# Ethernet.net
KiCad netlist of a schematic drawn in Altium Designer
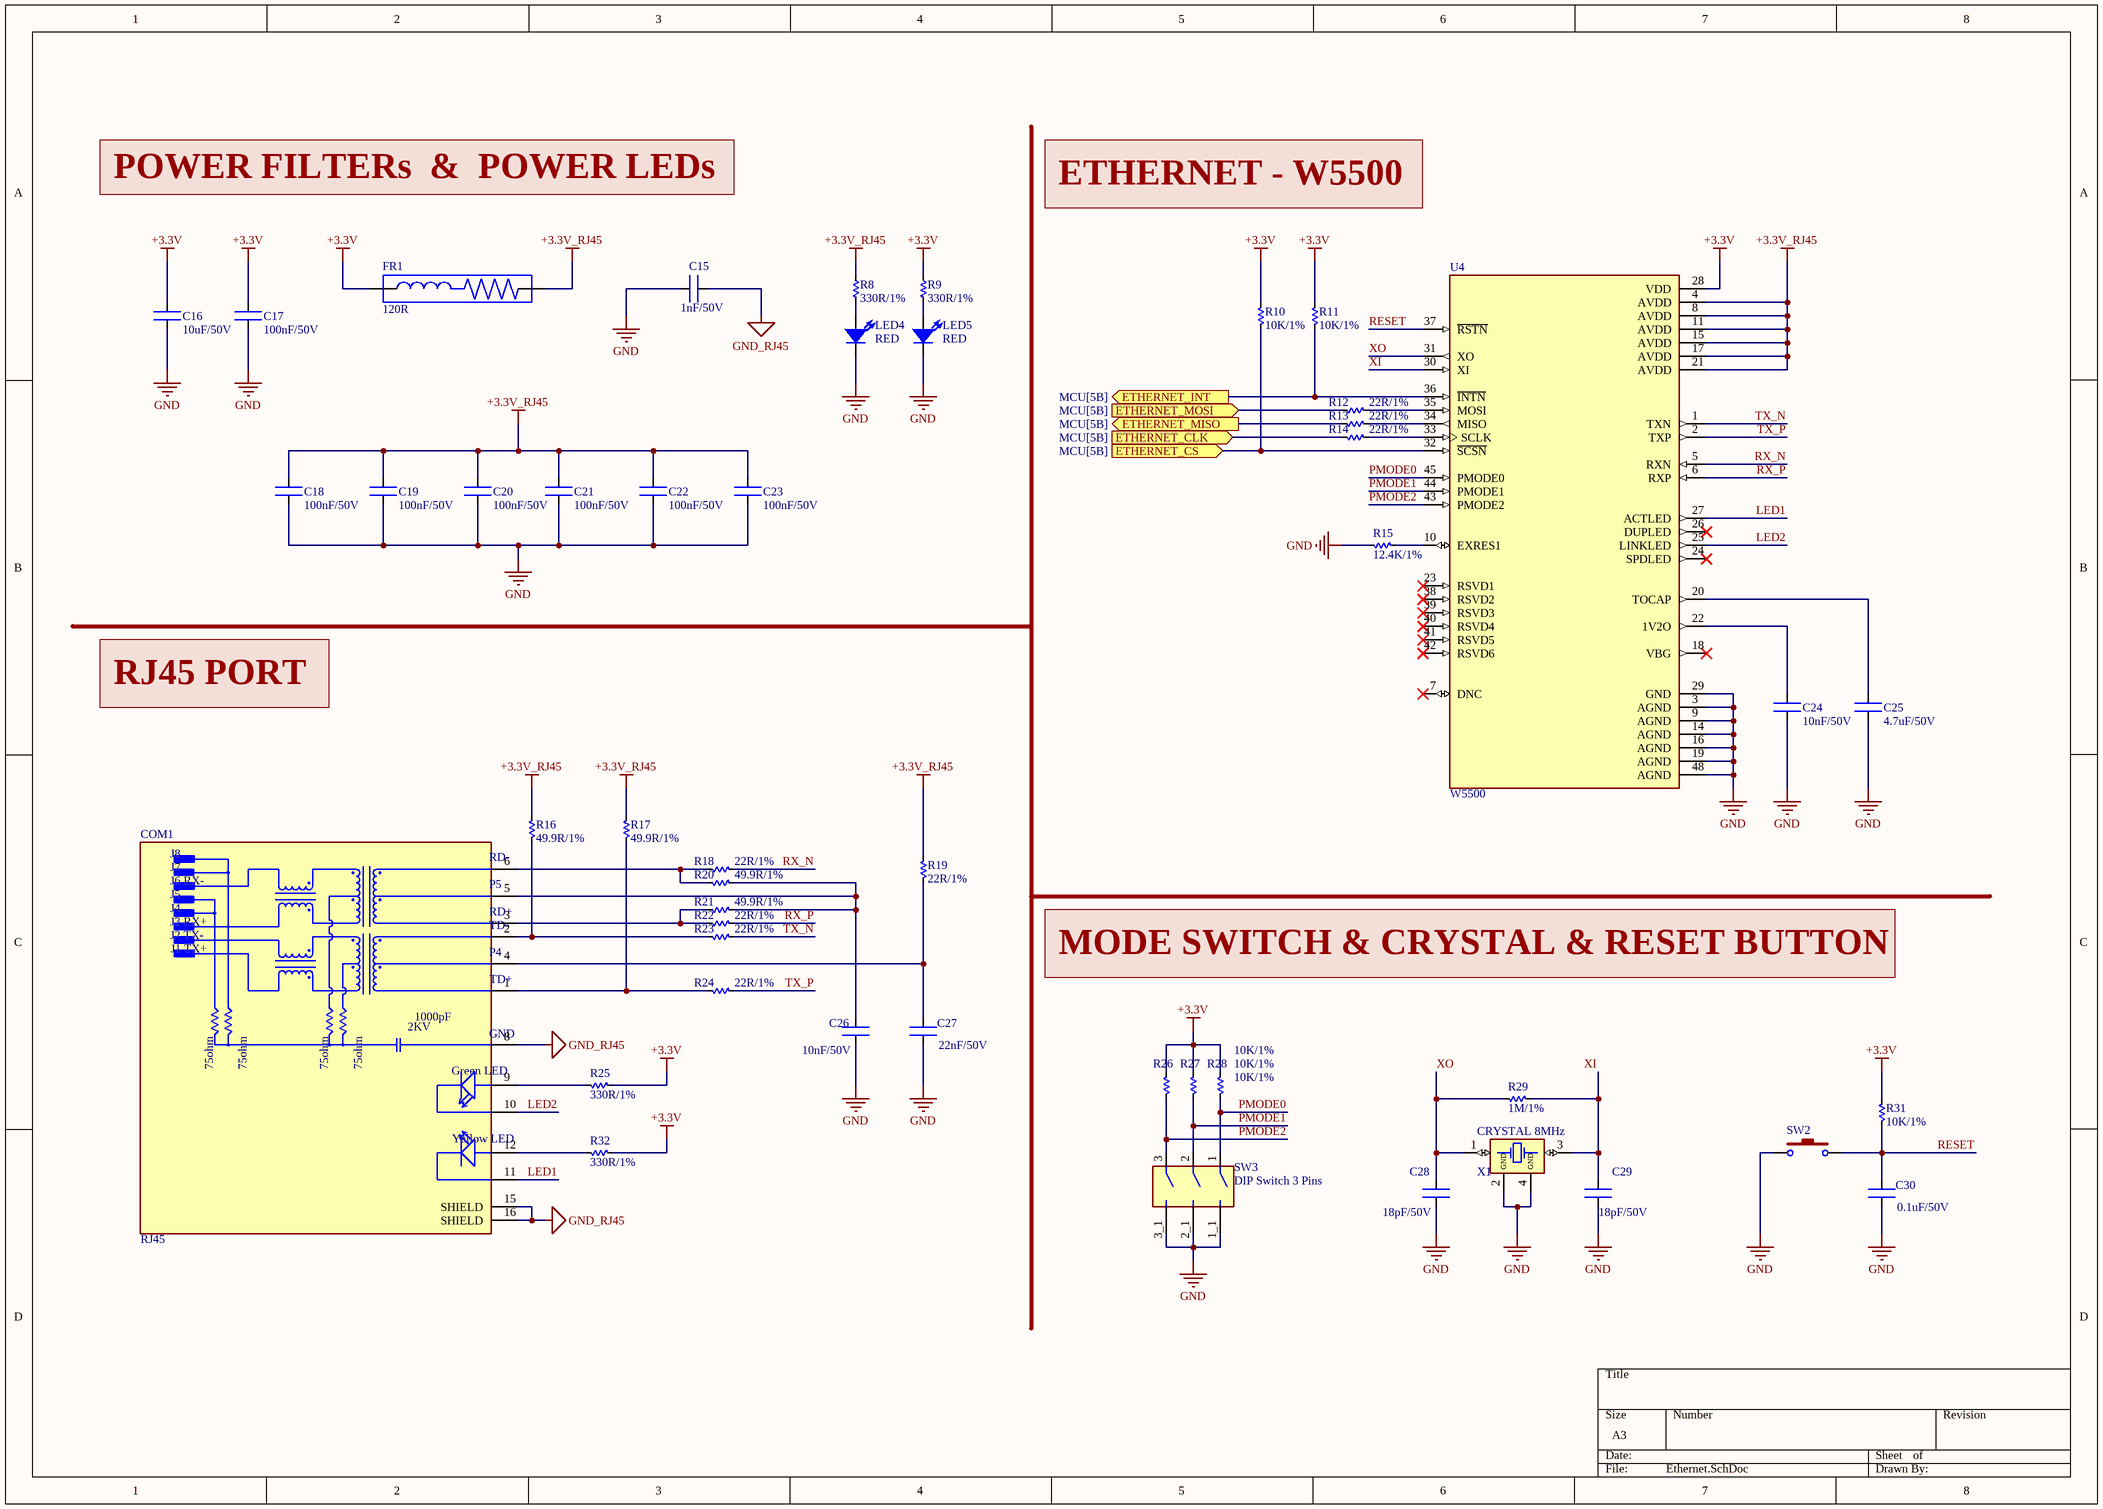
[diagram p0: Ethernet.SchDoc]

(export (version "E")
  (design (tool "Eeschema 10.0.6"))
  (components
    (comp (ref "C15")
      (value "1nF/50V")
      (footprint "CAP - 0603")
      (description "CAPACITOR SMD - KEMET")
      (libsource (lib "NewLibrary") (part "CAPACITOR"))
    )
    (comp (ref "C16")
      (value "10uF/50V")
      (footprint "CAP - 0603")
      (description "CAPACITOR SMD - KEMET")
      (libsource (lib "NewLibrary") (part "CAPACITOR"))
    )
    (comp (ref "C17")
      (value "100nF/50V")
      (footprint "CAP - 0603")
      (description "CAPACITOR SMD - KEMET")
      (libsource (lib "NewLibrary") (part "CAPACITOR"))
    )
    (comp (ref "C18")
      (value "100nF/50V")
      (footprint "CAP - 0603")
      (description "CAPACITOR SMD - KEMET")
      (libsource (lib "NewLibrary") (part "CAPACITOR"))
    )
    (comp (ref "C19")
      (value "100nF/50V")
      (footprint "CAP - 0603")
      (description "CAPACITOR SMD - KEMET")
      (libsource (lib "NewLibrary") (part "CAPACITOR"))
    )
    (comp (ref "C20")
      (value "100nF/50V")
      (footprint "CAP - 0603")
      (description "CAPACITOR SMD - KEMET")
      (libsource (lib "NewLibrary") (part "CAPACITOR"))
    )
    (comp (ref "C21")
      (value "100nF/50V")
      (footprint "CAP - 0603")
      (description "CAPACITOR SMD - KEMET")
      (libsource (lib "NewLibrary") (part "CAPACITOR"))
    )
    (comp (ref "C22")
      (value "100nF/50V")
      (footprint "CAP - 0603")
      (description "CAPACITOR SMD - KEMET")
      (libsource (lib "NewLibrary") (part "CAPACITOR"))
    )
    (comp (ref "C23")
      (value "100nF/50V")
      (footprint "CAP - 0603")
      (description "CAPACITOR SMD - KEMET")
      (libsource (lib "NewLibrary") (part "CAPACITOR"))
    )
    (comp (ref "C24")
      (value "10nF/50V")
      (footprint "CAP - 0603")
      (description "CAPACITOR SMD - KEMET")
      (libsource (lib "NewLibrary") (part "CAPACITOR"))
    )
    (comp (ref "C25")
      (value "4.7uF/50V")
      (footprint "CAP - 0603")
      (description "CAPACITOR SMD - KEMET")
      (libsource (lib "NewLibrary") (part "CAPACITOR"))
    )
    (comp (ref "C26")
      (value "10nF/50V")
      (footprint "CAP - 0603")
      (description "CAPACITOR SMD - KEMET")
      (libsource (lib "NewLibrary") (part "CAPACITOR"))
    )
    (comp (ref "C27")
      (value "22nF/50V")
      (footprint "CAP - 0603")
      (description "CAPACITOR SMD - KEMET")
      (libsource (lib "NewLibrary") (part "CAPACITOR"))
    )
    (comp (ref "C28")
      (value "18pF/50V")
      (footprint "CAP - 0603")
      (description "CAPACITOR SMD - KEMET")
      (libsource (lib "NewLibrary") (part "CAPACITOR"))
    )
    (comp (ref "C29")
      (value "18pF/50V")
      (footprint "CAP - 0603")
      (description "CAPACITOR SMD - KEMET")
      (libsource (lib "NewLibrary") (part "CAPACITOR"))
    )
    (comp (ref "C30")
      (value "0.1uF/50V")
      (footprint "CAP - 0603")
      (description "CAPACITOR SMD - KEMET")
      (libsource (lib "NewLibrary") (part "CAPACITOR"))
    )
    (comp (ref "COM1")
      (value "RJ45")
      (footprint "RJ45")
      (description "HR911105A")
      (libsource (lib "NewLibrary") (part "RJ45"))
    )
    (comp (ref "FR1")
      (value "120R")
      (footprint "FR-0805")
      (description "SMD")
      (libsource (lib "NewLibrary") (part "Ferrite Beads"))
    )
    (comp (ref "LED4")
      (value "RED")
      (footprint "RED_LED_0603")
      (description "LED SMD")
      (libsource (lib "NewLibrary") (part "LED_SMD"))
    )
    (comp (ref "LED5")
      (value "RED")
      (footprint "RED_LED_0603")
      (description "LED SMD")
      (libsource (lib "NewLibrary") (part "LED_SMD"))
    )
    (comp (ref "R8")
      (value "330R/1%")
      (footprint "RES - 0603")
      (description "Resistor SMD - YAGEO")
      (libsource (lib "NewLibrary") (part "RESISTOR"))
    )
    (comp (ref "R9")
      (value "330R/1%")
      (footprint "RES - 0603")
      (description "Resistor SMD - YAGEO")
      (libsource (lib "NewLibrary") (part "RESISTOR"))
    )
    (comp (ref "R10")
      (value "10K/1%")
      (footprint "RES - 0603")
      (description "Resistor SMD - YAGEO")
      (libsource (lib "NewLibrary") (part "RESISTOR"))
    )
    (comp (ref "R11")
      (value "10K/1%")
      (footprint "RES - 0603")
      (description "Resistor SMD - YAGEO")
      (libsource (lib "NewLibrary") (part "RESISTOR"))
    )
    (comp (ref "R12")
      (value "22R/1%")
      (footprint "RES - 0603")
      (description "Resistor SMD - YAGEO")
      (libsource (lib "NewLibrary") (part "RESISTOR"))
    )
    (comp (ref "R13")
      (value "22R/1%")
      (footprint "RES - 0603")
      (description "Resistor SMD - YAGEO")
      (libsource (lib "NewLibrary") (part "RESISTOR"))
    )
    (comp (ref "R14")
      (value "22R/1%")
      (footprint "RES - 0603")
      (description "Resistor SMD - YAGEO")
      (libsource (lib "NewLibrary") (part "RESISTOR"))
    )
    (comp (ref "R15")
      (value "12.4K/1%")
      (footprint "RES - 0603")
      (description "Resistor SMD - YAGEO")
      (libsource (lib "NewLibrary") (part "RESISTOR"))
    )
    (comp (ref "R16")
      (value "49.9R/1%")
      (footprint "RES - 0603")
      (description "Resistor SMD - YAGEO")
      (libsource (lib "NewLibrary") (part "RESISTOR"))
    )
    (comp (ref "R17")
      (value "49.9R/1%")
      (footprint "RES - 0603")
      (description "Resistor SMD - YAGEO")
      (libsource (lib "NewLibrary") (part "RESISTOR"))
    )
    (comp (ref "R18")
      (value "22R/1%")
      (footprint "RES - 0603")
      (description "Resistor SMD - YAGEO")
      (libsource (lib "NewLibrary") (part "RESISTOR"))
    )
    (comp (ref "R19")
      (value "22R/1%")
      (footprint "RES - 0603")
      (description "Resistor SMD - YAGEO")
      (libsource (lib "NewLibrary") (part "RESISTOR"))
    )
    (comp (ref "R20")
      (value "49.9R/1%")
      (footprint "RES - 0603")
      (description "Resistor SMD - YAGEO")
      (libsource (lib "NewLibrary") (part "RESISTOR"))
    )
    (comp (ref "R21")
      (value "49.9R/1%")
      (footprint "RES - 0603")
      (description "Resistor SMD - YAGEO")
      (libsource (lib "NewLibrary") (part "RESISTOR"))
    )
    (comp (ref "R22")
      (value "22R/1%")
      (footprint "RES - 0603")
      (description "Resistor SMD - YAGEO")
      (libsource (lib "NewLibrary") (part "RESISTOR"))
    )
    (comp (ref "R23")
      (value "22R/1%")
      (footprint "RES - 0603")
      (description "Resistor SMD - YAGEO")
      (libsource (lib "NewLibrary") (part "RESISTOR"))
    )
    (comp (ref "R24")
      (value "22R/1%")
      (footprint "RES - 0603")
      (description "Resistor SMD - YAGEO")
      (libsource (lib "NewLibrary") (part "RESISTOR"))
    )
    (comp (ref "R25")
      (value "330R/1%")
      (footprint "RES - 0603")
      (description "Resistor SMD - YAGEO")
      (libsource (lib "NewLibrary") (part "RESISTOR"))
    )
    (comp (ref "R26")
      (value "10K/1%")
      (footprint "RES - 0603")
      (description "Resistor SMD - YAGEO")
      (libsource (lib "NewLibrary") (part "RESISTOR"))
    )
    (comp (ref "R27")
      (value "10K/1%")
      (footprint "RES - 0603")
      (description "Resistor SMD - YAGEO")
      (libsource (lib "NewLibrary") (part "RESISTOR"))
    )
    (comp (ref "R28")
      (value "10K/1%")
      (footprint "RES - 0603")
      (description "Resistor SMD - YAGEO")
      (libsource (lib "NewLibrary") (part "RESISTOR"))
    )
    (comp (ref "R29")
      (value "1M/1%")
      (footprint "RES - 0603")
      (description "Resistor SMD - YAGEO")
      (libsource (lib "NewLibrary") (part "RESISTOR"))
    )
    (comp (ref "R31")
      (value "10K/1%")
      (footprint "RES - 0603")
      (description "Resistor SMD - YAGEO")
      (libsource (lib "NewLibrary") (part "RESISTOR"))
    )
    (comp (ref "R32")
      (value "330R/1%")
      (footprint "RES - 0603")
      (description "Resistor SMD - YAGEO")
      (libsource (lib "NewLibrary") (part "RESISTOR"))
    )
    (comp (ref "SW2")
      (value "Button 2 Pins")
      (footprint "SMD SWITCH 2 PINS")
      (description "SMD Button")
      (libsource (lib "NewLibrary") (part "Button 2 Pins"))
    )
    (comp (ref "SW3")
      (value "DIP Switch 3 Pins")
      (footprint "SMD - SW - 3Pins")
      (description "Switch DIP ON OFF SPST 3 Flush Slide 0.1A 20VDC Gull Wing 2000Cycles 2.54mm SMD T/R")
      (libsource (lib "NewLibrary") (part "DIP Switch 3 Pins"))
    )
    (comp (ref "U4")
      (value "W5500")
      (footprint "LQFP-48")
      (description "Hardwired TCP/IP embedded Ethernet controller")
      (libsource (lib "NewLibrary") (part "W5500"))
    )
    (comp (ref "X1")
      (value "CRYSTAL 8MHz")
      (footprint "crystal - 3.2 x 2.5 mm")
      (description "SMD CRYSTAL")
      (libsource (lib "NewLibrary") (part "CRYSTAL 8MHz"))
    )
  )
  (nets
    (net (code "1") (name "+3.3V") (class "Default")
      (node (ref "C16") (pin "2") (pinfunction "2_2") (pintype "passive"))
      (node (ref "C17") (pin "2") (pinfunction "2_2") (pintype "passive"))
      (node (ref "FR1") (pin "1") (pinfunction "1_1") (pintype "passive"))
      (node (ref "R10") (pin "2") (pinfunction "2_2") (pintype "passive"))
      (node (ref "R11") (pin "2") (pinfunction "2_2") (pintype "passive"))
      (node (ref "R25") (pin "1") (pinfunction "1_1") (pintype "passive"))
      (node (ref "R26") (pin "2") (pinfunction "2_2") (pintype "passive"))
      (node (ref "R27") (pin "2") (pinfunction "2_2") (pintype "passive"))
      (node (ref "R28") (pin "2") (pinfunction "2_2") (pintype "passive"))
      (node (ref "R31") (pin "1") (pinfunction "1_1") (pintype "passive"))
      (node (ref "R32") (pin "1") (pinfunction "1_1") (pintype "passive"))
      (node (ref "R9") (pin "1") (pinfunction "1_1") (pintype "passive"))
      (node (ref "U4") (pin "28") (pinfunction "VDD_28") (pintype "power_in"))
    )
    (net (code "2") (name "+3.3V_RJ45") (class "Default")
      (node (ref "C18") (pin "2") (pinfunction "2_2") (pintype "passive"))
      (node (ref "C19") (pin "2") (pinfunction "2_2") (pintype "passive"))
      (node (ref "C20") (pin "2") (pinfunction "2_2") (pintype "passive"))
      (node (ref "C21") (pin "2") (pinfunction "2_2") (pintype "passive"))
      (node (ref "C22") (pin "2") (pinfunction "2_2") (pintype "passive"))
      (node (ref "C23") (pin "2") (pinfunction "2_2") (pintype "passive"))
      (node (ref "FR1") (pin "2") (pinfunction "2_2") (pintype "passive"))
      (node (ref "R16") (pin "2") (pinfunction "2_2") (pintype "passive"))
      (node (ref "R17") (pin "2") (pinfunction "2_2") (pintype "passive"))
      (node (ref "R19") (pin "1") (pinfunction "1_1") (pintype "passive"))
      (node (ref "R8") (pin "1") (pinfunction "1_1") (pintype "passive"))
      (node (ref "U4") (pin "11") (pinfunction "AVDD_11") (pintype "power_in"))
      (node (ref "U4") (pin "15") (pinfunction "AVDD_15") (pintype "power_in"))
      (node (ref "U4") (pin "17") (pinfunction "AVDD_17") (pintype "power_in"))
      (node (ref "U4") (pin "21") (pinfunction "AVDD_21") (pintype "power_in"))
      (node (ref "U4") (pin "4") (pinfunction "AVDD_4") (pintype "power_in"))
      (node (ref "U4") (pin "8") (pinfunction "AVDD_8") (pintype "power_in"))
    )
    (net (code "3") (name "/ETHERNET_CLK") (class "Default")
      (node (ref "R14") (pin "2") (pinfunction "2_2") (pintype "passive"))
    )
    (net (code "4") (name "/ETHERNET_CS") (class "Default")
      (node (ref "R10") (pin "1") (pinfunction "1_1") (pintype "passive"))
      (node (ref "U4") (pin "32") (pinfunction "~{SCSN}_32") (pintype "input"))
    )
    (net (code "5") (name "/ETHERNET_INT") (class "Default")
      (node (ref "R11") (pin "1") (pinfunction "1_1") (pintype "passive"))
      (node (ref "U4") (pin "36") (pinfunction "~{INTN}_36") (pintype "input"))
    )
    (net (code "6") (name "/ETHERNET_MISO") (class "Default")
      (node (ref "R13") (pin "2") (pinfunction "2_2") (pintype "passive"))
    )
    (net (code "7") (name "/ETHERNET_MOSI") (class "Default")
      (node (ref "R12") (pin "2") (pinfunction "2_2") (pintype "passive"))
    )
    (net (code "8") (name "/LED1") (class "Default")
      (node (ref "COM1") (pin "11") (pinfunction "YC_11") (pintype "passive"))
      (node (ref "U4") (pin "27") (pinfunction "ACTLED_27") (pintype "output"))
    )
    (net (code "9") (name "/LED2") (class "Default")
      (node (ref "COM1") (pin "10") (pinfunction "GC_10") (pintype "passive"))
      (node (ref "U4") (pin "25") (pinfunction "LINKLED_25") (pintype "output"))
    )
    (net (code "10") (name "/PMODE0") (class "Default")
      (node (ref "R28") (pin "1") (pinfunction "1_1") (pintype "passive"))
      (node (ref "SW3") (pin "1") (pinfunction "1_1") (pintype "passive"))
      (node (ref "U4") (pin "45") (pinfunction "PMODE0_45") (pintype "input"))
    )
    (net (code "11") (name "/PMODE1") (class "Default")
      (node (ref "R27") (pin "1") (pinfunction "1_1") (pintype "passive"))
      (node (ref "SW3") (pin "2") (pinfunction "2_2") (pintype "passive"))
      (node (ref "U4") (pin "44") (pinfunction "PMODE1_44") (pintype "input"))
    )
    (net (code "12") (name "/PMODE2") (class "Default")
      (node (ref "R26") (pin "1") (pinfunction "1_1") (pintype "passive"))
      (node (ref "SW3") (pin "3") (pinfunction "3_3") (pintype "passive"))
      (node (ref "U4") (pin "43") (pinfunction "PMODE2_43") (pintype "input"))
    )
    (net (code "13") (name "/RESET") (class "Default")
      (node (ref "C30") (pin "2") (pinfunction "2_2") (pintype "passive"))
      (node (ref "R31") (pin "2") (pinfunction "2_2") (pintype "passive"))
      (node (ref "SW2") (pin "2") (pinfunction "2_2") (pintype "passive"))
      (node (ref "U4") (pin "37") (pinfunction "~{RSTN}_37") (pintype "input"))
    )
    (net (code "14") (name "/RX_N") (class "Default")
      (node (ref "R18") (pin "1") (pinfunction "1_1") (pintype "passive"))
      (node (ref "U4") (pin "5") (pinfunction "RXN_5") (pintype "input"))
    )
    (net (code "15") (name "/RX_P") (class "Default")
      (node (ref "R22") (pin "1") (pinfunction "1_1") (pintype "passive"))
      (node (ref "U4") (pin "6") (pinfunction "RXP_6") (pintype "input"))
    )
    (net (code "16") (name "/TX_N") (class "Default")
      (node (ref "R23") (pin "1") (pinfunction "1_1") (pintype "passive"))
      (node (ref "U4") (pin "1") (pinfunction "TXN_1") (pintype "output"))
    )
    (net (code "17") (name "/TX_P") (class "Default")
      (node (ref "R24") (pin "1") (pinfunction "1_1") (pintype "passive"))
      (node (ref "U4") (pin "2") (pinfunction "TXP_2") (pintype "output"))
    )
    (net (code "18") (name "/XI") (class "Default")
      (node (ref "C29") (pin "2") (pinfunction "2_2") (pintype "passive"))
      (node (ref "R29") (pin "1") (pinfunction "1_1") (pintype "passive"))
      (node (ref "U4") (pin "30") (pinfunction "XI_30") (pintype "input"))
      (node (ref "X1") (pin "3") (pinfunction "OUT/IN_3") (pintype "bidirectional"))
    )
    (net (code "19") (name "/XO") (class "Default")
      (node (ref "C28") (pin "2") (pinfunction "2_2") (pintype "passive"))
      (node (ref "R29") (pin "2") (pinfunction "2_2") (pintype "passive"))
      (node (ref "U4") (pin "31") (pinfunction "XO_31") (pintype "output"))
      (node (ref "X1") (pin "1") (pinfunction "IN/OUT_1") (pintype "bidirectional"))
    )
    (net (code "20") (name "GND") (class "Default")
      (node (ref "C15") (pin "1") (pinfunction "1_1") (pintype "passive"))
      (node (ref "C16") (pin "1") (pinfunction "1_1") (pintype "passive"))
      (node (ref "C17") (pin "1") (pinfunction "1_1") (pintype "passive"))
      (node (ref "C18") (pin "1") (pinfunction "1_1") (pintype "passive"))
      (node (ref "C19") (pin "1") (pinfunction "1_1") (pintype "passive"))
      (node (ref "C20") (pin "1") (pinfunction "1_1") (pintype "passive"))
      (node (ref "C21") (pin "1") (pinfunction "1_1") (pintype "passive"))
      (node (ref "C22") (pin "1") (pinfunction "1_1") (pintype "passive"))
      (node (ref "C23") (pin "1") (pinfunction "1_1") (pintype "passive"))
      (node (ref "C24") (pin "1") (pinfunction "1_1") (pintype "passive"))
      (node (ref "C25") (pin "1") (pinfunction "1_1") (pintype "passive"))
      (node (ref "C26") (pin "1") (pinfunction "1_1") (pintype "passive"))
      (node (ref "C27") (pin "1") (pinfunction "1_1") (pintype "passive"))
      (node (ref "C28") (pin "1") (pinfunction "1_1") (pintype "passive"))
      (node (ref "C29") (pin "1") (pinfunction "1_1") (pintype "passive"))
      (node (ref "C30") (pin "1") (pinfunction "1_1") (pintype "passive"))
      (node (ref "LED4") (pin "2") (pinfunction "2_2") (pintype "passive"))
      (node (ref "LED5") (pin "2") (pinfunction "2_2") (pintype "passive"))
      (node (ref "R15") (pin "1") (pinfunction "1_1") (pintype "passive"))
      (node (ref "SW2") (pin "1") (pinfunction "1_1") (pintype "passive"))
      (node (ref "SW3") (pin "1_1") (pinfunction "1_1_1_1") (pintype "passive"))
      (node (ref "SW3") (pin "2_1") (pinfunction "2_1_2_1") (pintype "passive"))
      (node (ref "SW3") (pin "3_1") (pinfunction "3_1_3_1") (pintype "passive"))
      (node (ref "U4") (pin "14") (pinfunction "AGND_14") (pintype "power_in"))
      (node (ref "U4") (pin "16") (pinfunction "AGND_16") (pintype "power_in"))
      (node (ref "U4") (pin "19") (pinfunction "AGND_19") (pintype "power_in"))
      (node (ref "U4") (pin "29") (pinfunction "GND_29") (pintype "passive"))
      (node (ref "U4") (pin "3") (pinfunction "AGND_3") (pintype "power_in"))
      (node (ref "U4") (pin "48") (pinfunction "AGND_48") (pintype "power_in"))
      (node (ref "U4") (pin "9") (pinfunction "AGND_9") (pintype "power_in"))
      (node (ref "X1") (pin "2") (pinfunction "GND_2") (pintype "power_in"))
      (node (ref "X1") (pin "4") (pinfunction "GND_4") (pintype "power_in"))
    )
    (net (code "21") (name "GND_RJ45") (class "Default")
      (node (ref "C15") (pin "2") (pinfunction "2_2") (pintype "passive"))
      (node (ref "COM1") (pin "15") (pinfunction "SHIELD_15") (pintype "passive"))
      (node (ref "COM1") (pin "16") (pinfunction "SHIELD_16") (pintype "passive"))
      (node (ref "COM1") (pin "8") (pinfunction "GND_8") (pintype "power_in"))
    )
    (net (code "22") (name "Net-(COM1-GA)") (class "Default")
      (node (ref "COM1") (pin "9") (pinfunction "GA_9") (pintype "passive"))
      (node (ref "R25") (pin "2") (pinfunction "2_2") (pintype "passive"))
    )
    (net (code "23") (name "Net-(COM1-P4)") (class "Default")
      (node (ref "C27") (pin "2") (pinfunction "2_2") (pintype "passive"))
      (node (ref "COM1") (pin "4") (pinfunction "P4_4") (pintype "passive"))
      (node (ref "R19") (pin "2") (pinfunction "2_2") (pintype "passive"))
    )
    (net (code "24") (name "Net-(COM1-P5)") (class "Default")
      (node (ref "C26") (pin "2") (pinfunction "2_2") (pintype "passive"))
      (node (ref "COM1") (pin "5") (pinfunction "P5_5") (pintype "passive"))
      (node (ref "R20") (pin "1") (pinfunction "1_1") (pintype "passive"))
      (node (ref "R21") (pin "1") (pinfunction "1_1") (pintype "passive"))
    )
    (net (code "25") (name "Net-(COM1-RD+)") (class "Default")
      (node (ref "COM1") (pin "3") (pinfunction "RD+_3") (pintype "passive"))
      (node (ref "R21") (pin "2") (pinfunction "2_2") (pintype "passive"))
      (node (ref "R22") (pin "2") (pinfunction "2_2") (pintype "passive"))
    )
    (net (code "26") (name "Net-(COM1-RD-)") (class "Default")
      (node (ref "COM1") (pin "6") (pinfunction "RD-_6") (pintype "passive"))
      (node (ref "R18") (pin "2") (pinfunction "2_2") (pintype "passive"))
      (node (ref "R20") (pin "2") (pinfunction "2_2") (pintype "passive"))
    )
    (net (code "27") (name "Net-(COM1-TD+)") (class "Default")
      (node (ref "COM1") (pin "1") (pinfunction "TD+_1") (pintype "passive"))
      (node (ref "R17") (pin "1") (pinfunction "1_1") (pintype "passive"))
      (node (ref "R24") (pin "2") (pinfunction "2_2") (pintype "passive"))
    )
    (net (code "28") (name "Net-(COM1-TD-)") (class "Default")
      (node (ref "COM1") (pin "2") (pinfunction "TD-_2") (pintype "passive"))
      (node (ref "R16") (pin "1") (pinfunction "1_1") (pintype "passive"))
      (node (ref "R23") (pin "2") (pinfunction "2_2") (pintype "passive"))
    )
    (net (code "29") (name "Net-(COM1-YA)") (class "Default")
      (node (ref "COM1") (pin "12") (pinfunction "YA_12") (pintype "passive"))
      (node (ref "R32") (pin "2") (pinfunction "2_2") (pintype "passive"))
    )
    (net (code "30") (name "Net-(LED4-Pad1)") (class "Default")
      (node (ref "LED4") (pin "1") (pinfunction "1_1") (pintype "passive"))
      (node (ref "R8") (pin "2") (pinfunction "2_2") (pintype "passive"))
    )
    (net (code "31") (name "Net-(LED5-Pad1)") (class "Default")
      (node (ref "LED5") (pin "1") (pinfunction "1_1") (pintype "passive"))
      (node (ref "R9") (pin "2") (pinfunction "2_2") (pintype "passive"))
    )
    (net (code "32") (name "Net-(U4-1V2O)") (class "Default")
      (node (ref "C24") (pin "2") (pinfunction "2_2") (pintype "passive"))
      (node (ref "U4") (pin "22") (pinfunction "1V2O_22") (pintype "output"))
    )
    (net (code "33") (name "Net-(U4-EXRES1)") (class "Default")
      (node (ref "R15") (pin "2") (pinfunction "2_2") (pintype "passive"))
      (node (ref "U4") (pin "10") (pinfunction "EXRES1_10") (pintype "bidirectional"))
    )
    (net (code "34") (name "Net-(U4-MISO)") (class "Default")
      (node (ref "R13") (pin "1") (pinfunction "1_1") (pintype "passive"))
      (node (ref "U4") (pin "34") (pinfunction "MISO_34") (pintype "output"))
    )
    (net (code "35") (name "Net-(U4-MOSI)") (class "Default")
      (node (ref "R12") (pin "1") (pinfunction "1_1") (pintype "passive"))
      (node (ref "U4") (pin "35") (pinfunction "MOSI_35") (pintype "input"))
    )
    (net (code "36") (name "Net-(U4-SCLK)") (class "Default")
      (node (ref "R14") (pin "1") (pinfunction "1_1") (pintype "passive"))
      (node (ref "U4") (pin "33") (pinfunction "SCLK_33") (pintype "input"))
    )
    (net (code "37") (name "Net-(U4-TOCAP)") (class "Default")
      (node (ref "C25") (pin "2") (pinfunction "2_2") (pintype "passive"))
      (node (ref "U4") (pin "20") (pinfunction "TOCAP_20") (pintype "output"))
    )
    (net (code "38") (name "unconnected-(U4-DNC-Pad7)") (class "Default")
      (node (ref "U4") (pin "7") (pinfunction "DNC_7") (pintype "bidirectional+no_connect"))
    )
    (net (code "39") (name "unconnected-(U4-DUPLED-Pad26)") (class "Default")
      (node (ref "U4") (pin "26") (pinfunction "DUPLED_26") (pintype "output+no_connect"))
    )
    (net (code "40") (name "unconnected-(U4-RSVD1-Pad23)") (class "Default")
      (node (ref "U4") (pin "23") (pinfunction "RSVD1_23") (pintype "input+no_connect"))
    )
    (net (code "41") (name "unconnected-(U4-RSVD2-Pad38)") (class "Default")
      (node (ref "U4") (pin "38") (pinfunction "RSVD2_38") (pintype "input+no_connect"))
    )
    (net (code "42") (name "unconnected-(U4-RSVD3-Pad39)") (class "Default")
      (node (ref "U4") (pin "39") (pinfunction "RSVD3_39") (pintype "input+no_connect"))
    )
    (net (code "43") (name "unconnected-(U4-RSVD4-Pad40)") (class "Default")
      (node (ref "U4") (pin "40") (pinfunction "RSVD4_40") (pintype "input+no_connect"))
    )
    (net (code "44") (name "unconnected-(U4-RSVD5-Pad41)") (class "Default")
      (node (ref "U4") (pin "41") (pinfunction "RSVD5_41") (pintype "input+no_connect"))
    )
    (net (code "45") (name "unconnected-(U4-RSVD6-Pad42)") (class "Default")
      (node (ref "U4") (pin "42") (pinfunction "RSVD6_42") (pintype "input+no_connect"))
    )
    (net (code "46") (name "unconnected-(U4-SPDLED-Pad24)") (class "Default")
      (node (ref "U4") (pin "24") (pinfunction "SPDLED_24") (pintype "output+no_connect"))
    )
    (net (code "47") (name "unconnected-(U4-VBG-Pad18)") (class "Default")
      (node (ref "U4") (pin "18") (pinfunction "VBG_18") (pintype "output+no_connect"))
    )
  )
)
